# Power.net
KiCad netlist of a schematic drawn in Altium Designer
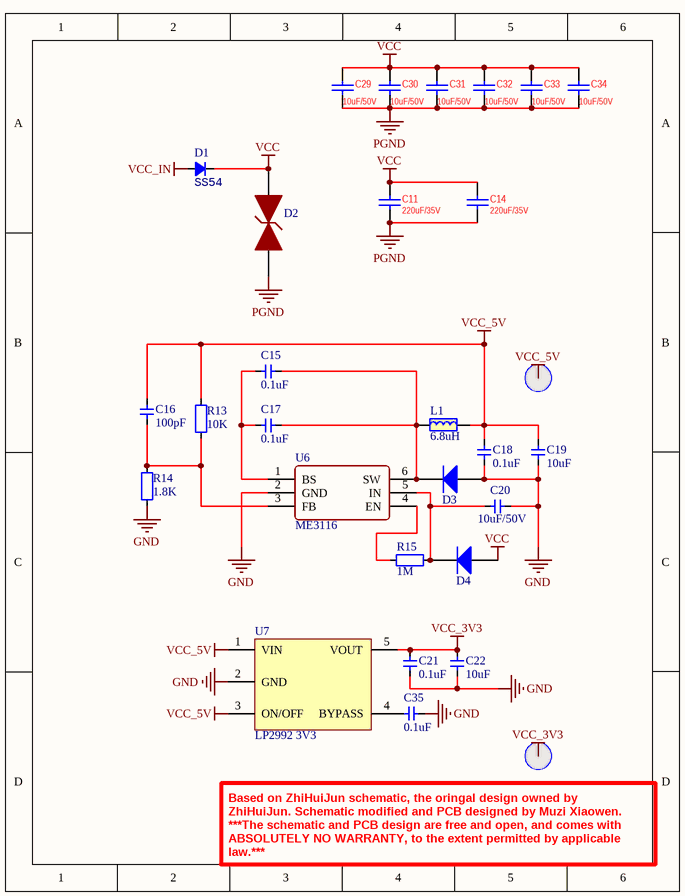
[diagram p0: Power.SchDoc]

(export (version "E")
  (design (tool "Eeschema 10.0.6"))
  (components
    (comp (ref "C11")
      (value "220uF/35V")
      (footprint "CAP-SMD_BD8.0-L8.3-W8.3-LS9.3-FD")
      (description "Capacitor, chip, ceramic")
      (fields (field (name "Comment") "220uF/25V"))
      (libsource (lib "OAKUSBFXS") (part "CAP"))
    )
    (comp (ref "C14")
      (value "220uF/35V")
      (footprint "CAP-SMD_BD8.0-L8.3-W8.3-LS9.3-FD")
      (description "Capacitor, chip, ceramic")
      (fields (field (name "Comment") "220uF/25V"))
      (libsource (lib "OAKUSBFXS") (part "CAP"))
    )
    (comp (ref "C15")
      (value "0.1uF")
      (footprint "motor42-lib:CAP_0402")
      (description "Capacitor")
      (libsource (lib "MyPcbLib") (part "电容-0402"))
    )
    (comp (ref "C16")
      (value "100pF")
      (footprint "CAP_0402")
      (description "Capacitor")
      (libsource (lib "MyPcbLib") (part "电容-0402"))
    )
    (comp (ref "C17")
      (value "0.1uF")
      (footprint "motor42-lib:CAP_0402")
      (description "Capacitor")
      (libsource (lib "MyPcbLib") (part "电容-0402"))
    )
    (comp (ref "C18")
      (value "0.1uF")
      (footprint "motor42-lib:CAP_0402")
      (description "Capacitor")
      (libsource (lib "MyPcbLib") (part "电容-0402"))
    )
    (comp (ref "C19")
      (value "10uF")
      (footprint "CAP_0402")
      (description "Capacitor")
      (libsource (lib "MyPcbLib") (part "电容-0402"))
    )
    (comp (ref "C20")
      (value "10uF/50V")
      (footprint "1206-CAP")
      (description "Capacitor")
      (libsource (lib "MyPcbLib") (part "电容-0402"))
    )
    (comp (ref "C21")
      (value "0.1uF")
      (footprint "motor42-lib:CAP_0402")
      (description "Capacitor")
      (libsource (lib "MyPcbLib") (part "电容-0402"))
    )
    (comp (ref "C22")
      (value "10uF")
      (footprint "CAP_0402")
      (description "Capacitor")
      (libsource (lib "MyPcbLib") (part "电容-0402"))
    )
    (comp (ref "C29")
      (value "10uF/50V")
      (footprint "1206-CAP")
      (description "Capacitor, chip, ceramic")
      (libsource (lib "OAKUSBFXS") (part "CAP"))
    )
    (comp (ref "C30")
      (value "10uF/50V")
      (footprint "1206-CAP")
      (description "Capacitor, chip, ceramic")
      (libsource (lib "OAKUSBFXS") (part "CAP"))
    )
    (comp (ref "C31")
      (value "10uF/50V")
      (footprint "1206-CAP")
      (description "Capacitor, chip, ceramic")
      (libsource (lib "OAKUSBFXS") (part "CAP"))
    )
    (comp (ref "C32")
      (value "10uF/50V")
      (footprint "1206-CAP")
      (description "Capacitor, chip, ceramic")
      (libsource (lib "OAKUSBFXS") (part "CAP"))
    )
    (comp (ref "C33")
      (value "10uF/50V")
      (footprint "1206-CAP")
      (description "Capacitor, chip, ceramic")
      (libsource (lib "OAKUSBFXS") (part "CAP"))
    )
    (comp (ref "C34")
      (value "10uF/50V")
      (footprint "1206-CAP")
      (description "Capacitor, chip, ceramic")
      (libsource (lib "OAKUSBFXS") (part "CAP"))
    )
    (comp (ref "C35")
      (value "0.1uF")
      (footprint "motor42-lib:CAP_0402")
      (description "Capacitor")
      (libsource (lib "MyPcbLib") (part "电容-0402"))
    )
    (comp (ref "D1")
      (value "SS54")
      (footprint "DO-214AC")
      (description "Diode")
      (libsource (lib "KitSprout") (part "Diode_SMA"))
    )
    (comp (ref "D2")
      (value "SMBJ28CA")
      (footprint "SMBJ-CA_MFG")
      (libsource (lib "MyPcbLib") (part "SMBJ28CA"))
    )
    (comp (ref "D3")
      (value "二极管-5819W")
      (footprint "SOD-323")
      (description "40V")
      (libsource (lib "MyPcbLib") (part "二极管-5819W"))
    )
    (comp (ref "D4")
      (value "二极管-5819W")
      (footprint "SOD-323")
      (description "40V")
      (libsource (lib "MyPcbLib") (part "二极管-5819W"))
    )
    (comp (ref "L1") (value "6.8uH") (footprint "IND-201612") (libsource (lib "MyPcbLib") (part "电感-201612")))
    (comp (ref "R13")
      (value "10K")
      (footprint "RES_0402")
      (description "Resistor")
      (libsource (lib "MyPcbLib") (part "电阻-0402"))
    )
    (comp (ref "R14")
      (value "1.8K")
      (footprint "RES_0402")
      (description "Resistor")
      (libsource (lib "MyPcbLib") (part "电阻-0402"))
    )
    (comp (ref "R15")
      (value "1M")
      (footprint "RES_0402")
      (description "Resistor")
      (libsource (lib "") (part "电阻-0402_1"))
    )
    (comp (ref "T1") (value "测试点") (footprint "TEST_PT") (libsource (lib "MyPcbLib") (part "测试点")))
    (comp (ref "T2") (value "测试点") (footprint "TEST_PT") (libsource (lib "MyPcbLib") (part "测试点")))
    (comp (ref "U6")
      (value "ME3116")
      (footprint "SOT23-6")
      (description "DC-DC")
      (libsource (lib "MyPcbLib") (part "ME3116"))
    )
    (comp (ref "U7")
      (value "LP2992 3V3")
      (footprint "SOT23-5")
      (description "LDO")
      (libsource (lib "MyPcbLib") (part "LP2992"))
    )
  )
  (nets
    (net (code "1") (name "GND") (class "Default")
      (node (ref "C18") (pin "1") (pinfunction "1_1") (pintype "passive"))
      (node (ref "C19") (pin "1") (pinfunction "1_1") (pintype "passive"))
      (node (ref "C20") (pin "1") (pinfunction "1_1") (pintype "passive"))
      (node (ref "C21") (pin "1") (pinfunction "1_1") (pintype "passive"))
      (node (ref "C22") (pin "1") (pinfunction "1_1") (pintype "passive"))
      (node (ref "C35") (pin "1") (pinfunction "1_1") (pintype "passive"))
      (node (ref "D3") (pin "1") (pinfunction "A_1") (pintype "passive"))
      (node (ref "R14") (pin "1") (pinfunction "1_1") (pintype "passive"))
      (node (ref "U6") (pin "2") (pinfunction "GND_2") (pintype "passive"))
      (node (ref "U7") (pin "2") (pinfunction "GND_2") (pintype "passive"))
    )
    (net (code "2") (name "Net-(D3-K)") (class "Default")
      (node (ref "C15") (pin "1") (pinfunction "1_1") (pintype "passive"))
      (node (ref "C17") (pin "1") (pinfunction "1_1") (pintype "passive"))
      (node (ref "D3") (pin "2") (pinfunction "K_2") (pintype "passive"))
      (node (ref "L1") (pin "1") (pintype "passive"))
      (node (ref "U6") (pin "6") (pinfunction "SW_6") (pintype "passive"))
    )
    (net (code "3") (name "Net-(D4-K)") (class "Default")
      (node (ref "C20") (pin "2") (pinfunction "2_2") (pintype "passive"))
      (node (ref "D4") (pin "2") (pinfunction "K_2") (pintype "passive"))
      (node (ref "R15") (pin "1") (pinfunction "1_1") (pintype "passive"))
      (node (ref "U6") (pin "5") (pinfunction "IN_5") (pintype "passive"))
    )
    (net (code "4") (name "Net-(U6-BS)") (class "Default")
      (node (ref "C15") (pin "2") (pinfunction "2_2") (pintype "passive"))
      (node (ref "C17") (pin "2") (pinfunction "2_2") (pintype "passive"))
      (node (ref "U6") (pin "1") (pinfunction "BS_1") (pintype "passive"))
    )
    (net (code "5") (name "Net-(U6-EN)") (class "Default")
      (node (ref "R15") (pin "2") (pinfunction "2_2") (pintype "passive"))
      (node (ref "U6") (pin "4") (pinfunction "EN_4") (pintype "passive"))
    )
    (net (code "6") (name "Net-(U6-FB)") (class "Default")
      (node (ref "C16") (pin "2") (pinfunction "2_2") (pintype "passive"))
      (node (ref "R13") (pin "1") (pinfunction "1_1") (pintype "passive"))
      (node (ref "R14") (pin "2") (pinfunction "2_2") (pintype "passive"))
      (node (ref "U6") (pin "3") (pinfunction "FB_3") (pintype "passive"))
    )
    (net (code "7") (name "Net-(U7-BYPASS)") (class "Default")
      (node (ref "C35") (pin "2") (pinfunction "2_2") (pintype "passive"))
      (node (ref "U7") (pin "4") (pinfunction "BYPASS_4") (pintype "passive"))
    )
    (net (code "8") (name "PGND") (class "Default")
      (node (ref "C11") (pin "2") (pinfunction "2_2") (pintype "passive"))
      (node (ref "C14") (pin "2") (pinfunction "2_2") (pintype "passive"))
      (node (ref "C29") (pin "2") (pinfunction "2_2") (pintype "passive"))
      (node (ref "C30") (pin "2") (pinfunction "2_2") (pintype "passive"))
      (node (ref "C31") (pin "2") (pinfunction "2_2") (pintype "passive"))
      (node (ref "C32") (pin "2") (pinfunction "2_2") (pintype "passive"))
      (node (ref "C33") (pin "2") (pinfunction "2_2") (pintype "passive"))
      (node (ref "C34") (pin "2") (pinfunction "2_2") (pintype "passive"))
      (node (ref "D2") (pin "1") (pinfunction "1_1") (pintype "passive"))
    )
    (net (code "9") (name "VCC") (class "Default")
      (node (ref "C11") (pin "1") (pinfunction "1_1") (pintype "passive"))
      (node (ref "C14") (pin "1") (pinfunction "1_1") (pintype "passive"))
      (node (ref "C29") (pin "1") (pinfunction "1_1") (pintype "passive"))
      (node (ref "C30") (pin "1") (pinfunction "1_1") (pintype "passive"))
      (node (ref "C31") (pin "1") (pinfunction "1_1") (pintype "passive"))
      (node (ref "C32") (pin "1") (pinfunction "1_1") (pintype "passive"))
      (node (ref "C33") (pin "1") (pinfunction "1_1") (pintype "passive"))
      (node (ref "C34") (pin "1") (pinfunction "1_1") (pintype "passive"))
      (node (ref "D1") (pin "2") (pinfunction "K_2") (pintype "passive"))
      (node (ref "D2") (pin "2") (pinfunction "2_2") (pintype "passive"))
      (node (ref "D4") (pin "1") (pinfunction "A_1") (pintype "passive"))
    )
    (net (code "10") (name "VCC_3V3") (class "Default")
      (node (ref "C21") (pin "2") (pinfunction "2_2") (pintype "passive"))
      (node (ref "C22") (pin "2") (pinfunction "2_2") (pintype "passive"))
      (node (ref "T2") (pin "0") (pinfunction "0_0") (pintype "passive"))
      (node (ref "U7") (pin "5") (pinfunction "VOUT_5") (pintype "passive"))
    )
    (net (code "11") (name "VCC_5V") (class "Default")
      (node (ref "C16") (pin "1") (pinfunction "1_1") (pintype "passive"))
      (node (ref "C18") (pin "2") (pinfunction "2_2") (pintype "passive"))
      (node (ref "C19") (pin "2") (pinfunction "2_2") (pintype "passive"))
      (node (ref "L1") (pin "2") (pinfunction "2_2") (pintype "passive"))
      (node (ref "R13") (pin "2") (pinfunction "2_2") (pintype "passive"))
      (node (ref "T1") (pin "0") (pinfunction "0_0") (pintype "passive"))
      (node (ref "U7") (pin "1") (pinfunction "VIN_1") (pintype "passive"))
      (node (ref "U7") (pin "3") (pinfunction "ON/OFF_3") (pintype "passive"))
    )
    (net (code "12") (name "VCC_IN") (class "Default")
      (node (ref "D1") (pin "1") (pinfunction "A_1") (pintype "passive"))
    )
  )
)
